# Circuito.net
KiCad netlist of a schematic drawn in EAGLE
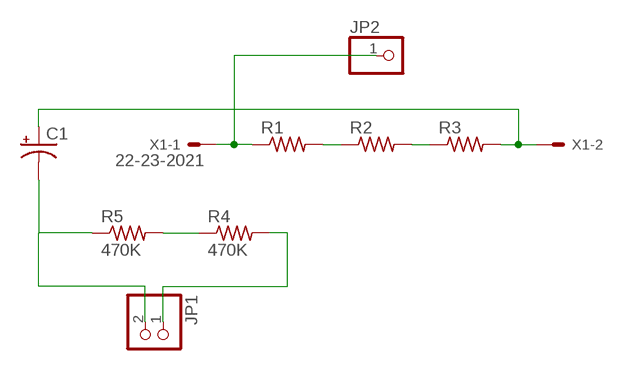
[diagram p0: schematic, sheet 1]

(export (version "E")
  (design (tool "Eeschema 10.0.6"))
  (components
    (comp (ref "C1")
      (value "CPOL-USE2.5-7")
      (footprint "eagle-import:E2,5-7")
      (libsource (lib "eagle-import") (part "CPOL-USE2.5-7"))
    )
    (comp (ref "JP1")
      (value "PINHD-1X2")
      (footprint "eagle-import:1X02")
      (libsource (lib "eagle-import") (part "PINHD-1X2"))
    )
    (comp (ref "JP2")
      (value "PINHD-1X1")
      (footprint "eagle-import:1X01")
      (libsource (lib "eagle-import") (part "PINHD-1X1"))
    )
    (comp (ref "R1")
      (value "R-US_0204/7")
      (footprint "eagle-import:0204_7")
      (libsource (lib "eagle-import") (part "resistor_348_R-US_0204/7"))
    )
    (comp (ref "R2")
      (value "R-US_0204/7")
      (footprint "eagle-import:0204_7")
      (libsource (lib "eagle-import") (part "resistor_348_R-US_0204/7"))
    )
    (comp (ref "R3")
      (value "R-US_0204/7")
      (footprint "eagle-import:0204_7")
      (libsource (lib "eagle-import") (part "resistor_348_R-US_0204/7"))
    )
    (comp (ref "R4")
      (value "470K")
      (footprint "eagle-import:0204_7")
      (libsource (lib "eagle-import") (part "R-US_0204/7"))
    )
    (comp (ref "R5")
      (value "470K")
      (footprint "eagle-import:0204_7")
      (libsource (lib "eagle-import") (part "R-US_0204/7"))
    )
    (comp (ref "X1")
      (value "22-23-2021")
      (footprint "eagle-import:22-23-2021")
      (fields (field (name "MF") "MOLEX"))
      (libsource (lib "eagle-import") (part "22-23-2021"))
    )
  )
  (nets
    (net (code "1") (name "Net-(C1-Pad-)") (class "Default")
      (node (ref "C1") (pin "-") (pinfunction "-_-") (pintype "passive"))
      (node (ref "JP1") (pin "2") (pinfunction "2_2") (pintype "passive"))
      (node (ref "R5") (pin "1") (pinfunction "1_1") (pintype "passive"))
    )
    (net (code "2") (name "Net-(JP1-Pad1)") (class "Default")
      (node (ref "JP1") (pin "1") (pinfunction "1_1") (pintype "passive"))
      (node (ref "R4") (pin "2") (pinfunction "2_2") (pintype "passive"))
    )
    (net (code "3") (name "Net-(R1-Pad2)") (class "Default")
      (node (ref "R1") (pin "2") (pinfunction "2_2") (pintype "passive"))
      (node (ref "R2") (pin "1") (pinfunction "1_1") (pintype "passive"))
    )
    (net (code "4") (name "Net-(R2-Pad2)") (class "Default")
      (node (ref "R2") (pin "2") (pinfunction "2_2") (pintype "passive"))
      (node (ref "R3") (pin "1") (pinfunction "1_1") (pintype "passive"))
    )
    (net (code "5") (name "Net-(R4-Pad1)") (class "Default")
      (node (ref "R4") (pin "1") (pinfunction "1_1") (pintype "passive"))
      (node (ref "R5") (pin "2") (pinfunction "2_2") (pintype "passive"))
    )
    (net (code "6") (name "Net-(X1A-S)") (class "Default")
      (node (ref "JP2") (pin "1") (pinfunction "1_1") (pintype "passive"))
      (node (ref "R1") (pin "1") (pinfunction "1_1") (pintype "passive"))
      (node (ref "X1") (pin "1") (pinfunction "S_1") (pintype "passive"))
    )
    (net (code "7") (name "Net-(X1B-S)") (class "Default")
      (node (ref "C1") (pin "+") (pinfunction "+_+") (pintype "passive"))
      (node (ref "R3") (pin "2") (pinfunction "2_2") (pintype "passive"))
      (node (ref "X1") (pin "2") (pinfunction "S_2") (pintype "passive"))
    )
  )
)
